# DE-020717_2.net
KiCad netlist of a schematic drawn in Altium Designer
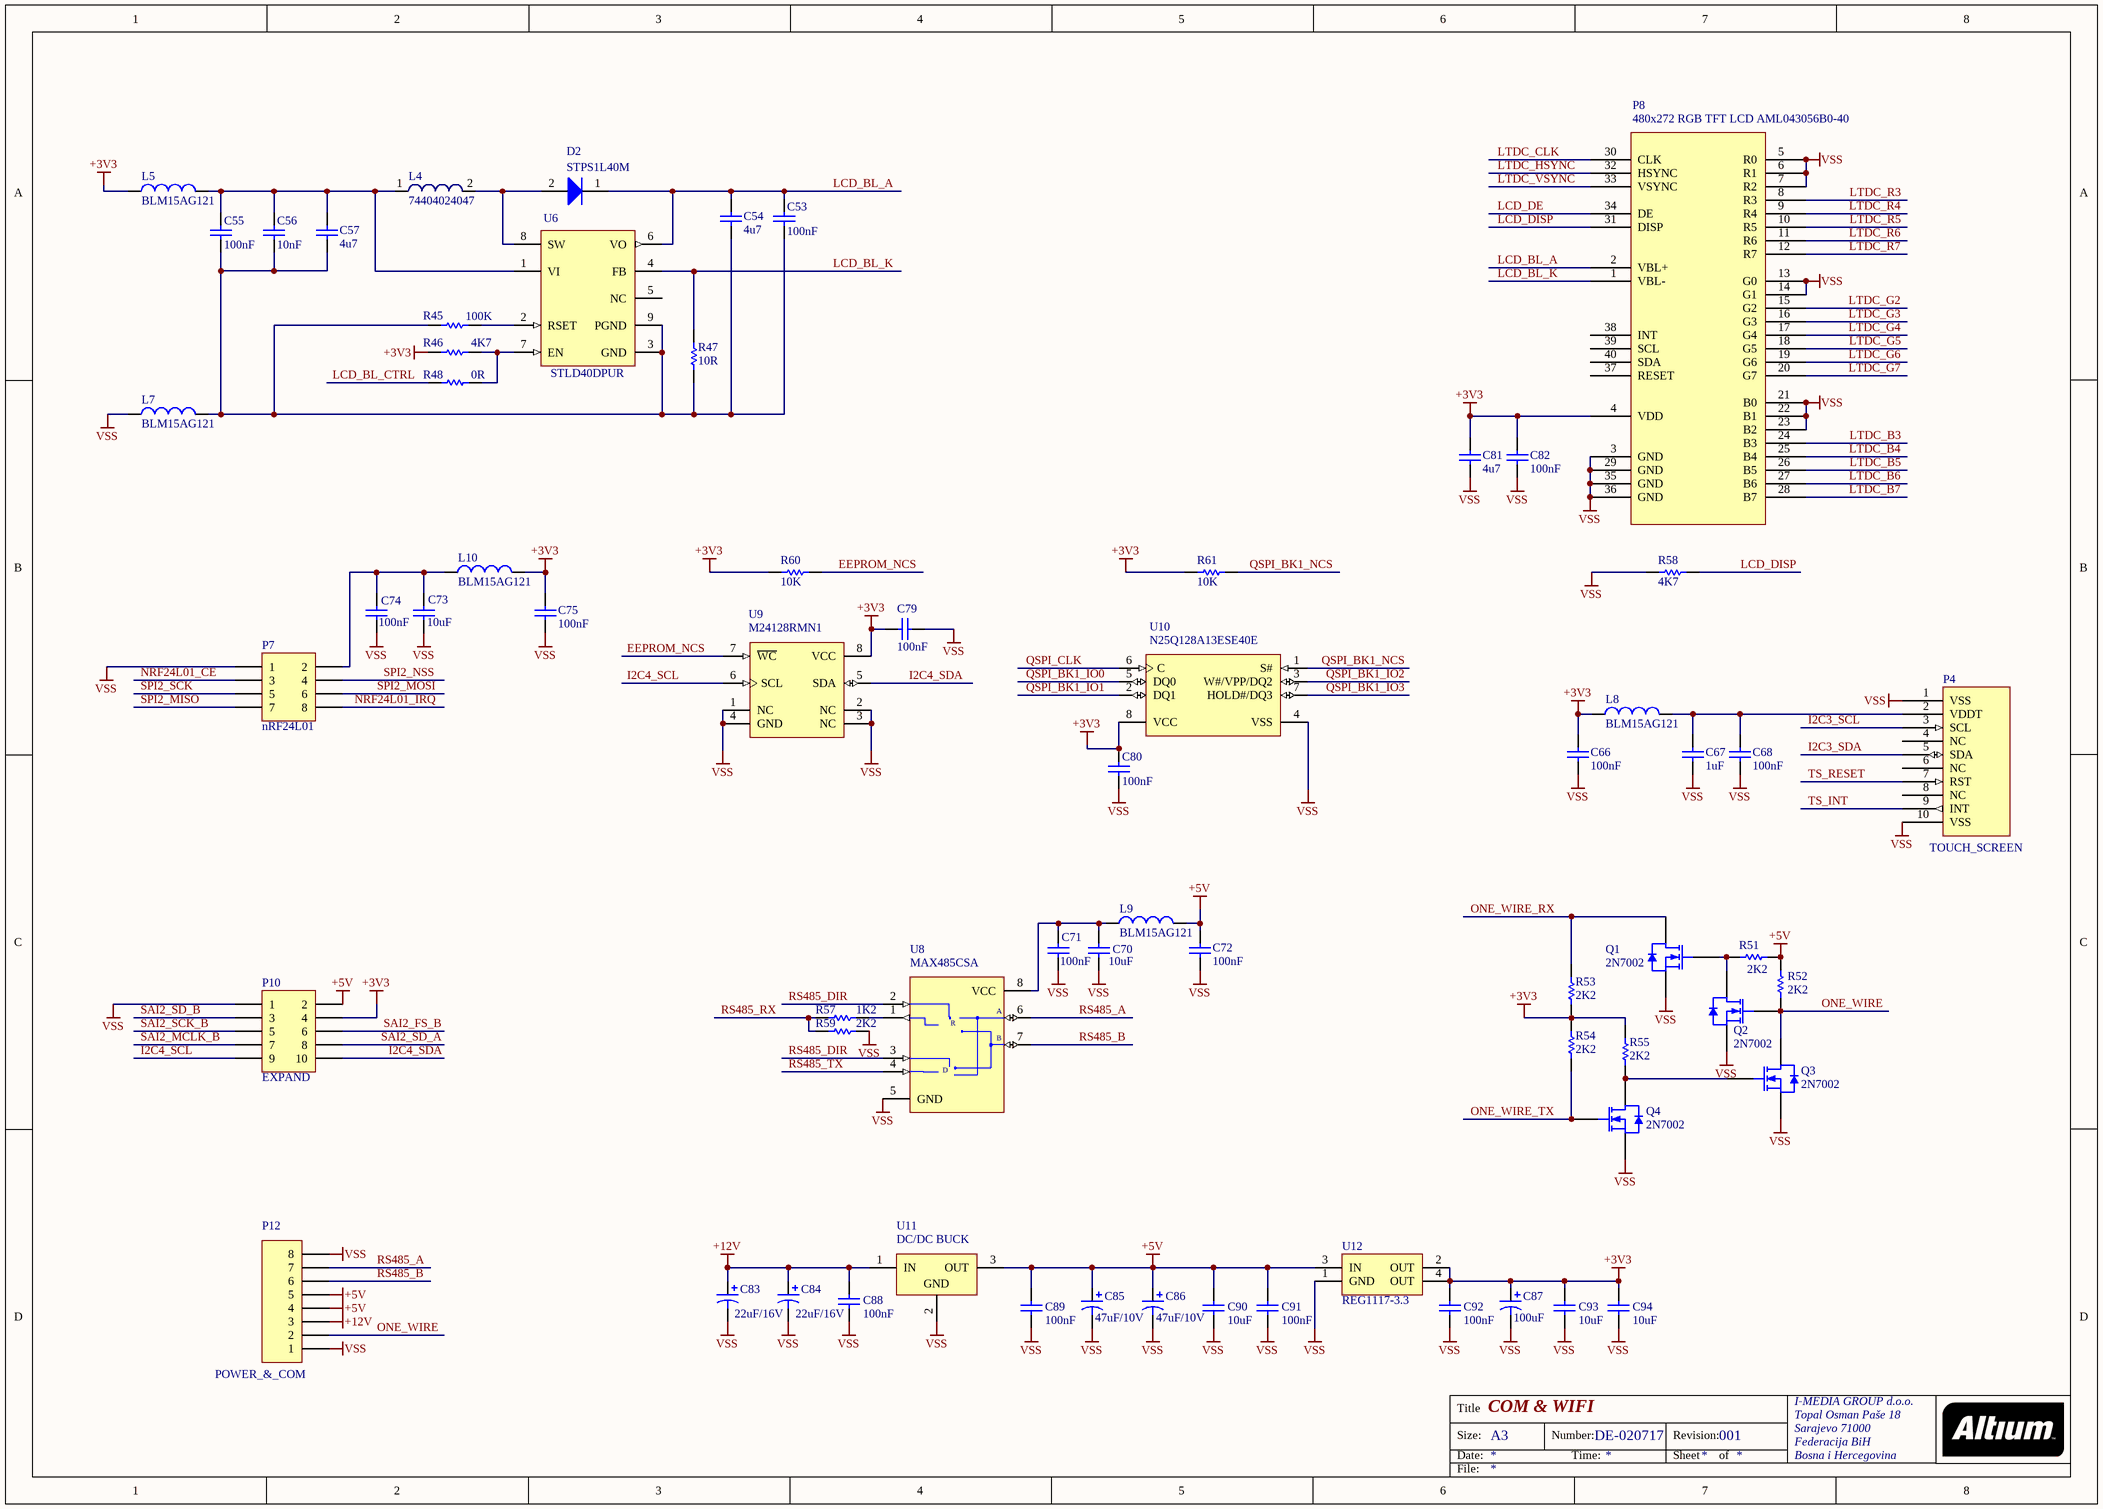
[diagram p0: DE-020717_2.SchDoc]

(export (version "E")
  (design (tool "Eeschema 10.0.6"))
  (components
    (comp (ref "C53")
      (value "100nF")
      (footprint "0603")
      (description "Ceramic Chip Capacitor - Standard")
      (fields (field (name "PUBLISHER") "Altium Limited"))
      (libsource (lib "KEMET Chip Capacitor") (part "C0603"))
    )
    (comp (ref "C54")
      (value "4u7")
      (footprint "0805")
      (description "Ceramic Chip Capacitor - Standard")
      (fields (field (name "PUBLISHER") "Altium Limited"))
      (libsource (lib "DE-020717") (part "C0805"))
    )
    (comp (ref "C55")
      (value "100nF")
      (footprint "0603")
      (description "Ceramic Chip Capacitor - Standard")
      (fields (field (name "PUBLISHER") "Altium Limited"))
      (libsource (lib "KEMET Chip Capacitor") (part "C0603"))
    )
    (comp (ref "C56")
      (value "10nF")
      (footprint "0603")
      (description "Ceramic Chip Capacitor - Standard")
      (fields (field (name "Comment") "100nF") (field (name "PUBLISHER") "Altium Limited"))
      (libsource (lib "KEMET Chip Capacitor") (part "C0603"))
    )
    (comp (ref "C57")
      (value "4u7")
      (footprint "0805")
      (description "Ceramic Chip Capacitor - Standard")
      (fields (field (name "PUBLISHER") "Altium Limited"))
      (libsource (lib "DE-020717") (part "C0805"))
    )
    (comp (ref "C66")
      (value "100nF")
      (footprint "0603")
      (description "Ceramic Chip Capacitor - Standard")
      (fields (field (name "PUBLISHER") "Altium Limited"))
      (libsource (lib "DE-020717") (part "C0603"))
    )
    (comp (ref "C67")
      (value "1uF")
      (footprint "0603")
      (description "Ceramic Chip Capacitor - Standard")
      (fields (field (name "PUBLISHER") "Altium Limited"))
      (libsource (lib "DE-020717") (part "C0603"))
    )
    (comp (ref "C68")
      (value "100nF")
      (footprint "0603")
      (description "Ceramic Chip Capacitor - Standard")
      (fields (field (name "PUBLISHER") "Altium Limited"))
      (libsource (lib "DE-020717") (part "C0603"))
    )
    (comp (ref "C70")
      (value "10uF")
      (footprint "0805")
      (description "Ceramic Chip Capacitor - Standard")
      (fields (field (name "Comment") "4u7") (field (name "PUBLISHER") "Altium Limited"))
      (libsource (lib "DE-020717") (part "C0805"))
    )
    (comp (ref "C71")
      (value "100nF")
      (footprint "0603")
      (description "Ceramic Chip Capacitor - Standard")
      (fields (field (name "PUBLISHER") "Altium Limited"))
      (libsource (lib "DE-020717") (part "C0603"))
    )
    (comp (ref "C72")
      (value "100nF")
      (footprint "0603")
      (description "Ceramic Chip Capacitor - Standard")
      (fields (field (name "PUBLISHER") "Altium Limited"))
      (libsource (lib "DE-020717") (part "C0603"))
    )
    (comp (ref "C73")
      (value "10uF")
      (footprint "0805")
      (description "Ceramic Chip Capacitor - Standard")
      (fields (field (name "Comment") "4u7") (field (name "PUBLISHER") "Altium Limited"))
      (libsource (lib "DE-020717") (part "C0805"))
    )
    (comp (ref "C74")
      (value "100nF")
      (footprint "0603")
      (description "Ceramic Chip Capacitor - Standard")
      (fields (field (name "PUBLISHER") "Altium Limited"))
      (libsource (lib "DE-020717") (part "C0603"))
    )
    (comp (ref "C75")
      (value "100nF")
      (footprint "0603")
      (description "Ceramic Chip Capacitor - Standard")
      (fields (field (name "PUBLISHER") "Altium Limited"))
      (libsource (lib "DE-020717") (part "C0603"))
    )
    (comp (ref "C79")
      (value "100nF")
      (footprint "0603")
      (description "Ceramic Chip Capacitor - Standard")
      (fields (field (name "PUBLISHER") "Altium Limited"))
      (libsource (lib "KEMET Chip Capacitor") (part "C0603"))
    )
    (comp (ref "C80")
      (value "100nF")
      (footprint "0603")
      (description "Ceramic Chip Capacitor - Standard")
      (fields (field (name "PUBLISHER") "Altium Limited"))
      (libsource (lib "KEMET Chip Capacitor") (part "C0603"))
    )
    (comp (ref "C81")
      (value "4u7")
      (footprint "0805")
      (description "Ceramic Chip Capacitor - Standard")
      (fields (field (name "PUBLISHER") "Altium Limited"))
      (libsource (lib "DE-020717") (part "C0805"))
    )
    (comp (ref "C82")
      (value "100nF")
      (footprint "0603")
      (description "Ceramic Chip Capacitor - Standard")
      (fields (field (name "PUBLISHER") "Altium Limited"))
      (libsource (lib "DE-020717") (part "C0603"))
    )
    (comp (ref "C83")
      (value "22uF/16V")
      (footprint "3528")
      (fields (field (name "PUBLISHER") "Altium Limited"))
      (libsource (lib "Vishay Sprague Tantalum Chip Capacitor") (part "293D156X0004B2"))
    )
    (comp (ref "C84")
      (value "22uF/16V")
      (footprint "3528")
      (fields (field (name "PUBLISHER") "Altium Limited"))
      (libsource (lib "Vishay Sprague Tantalum Chip Capacitor") (part "293D156X0004B2"))
    )
    (comp (ref "C85")
      (value "47uF/10V")
      (footprint "3528")
      (fields (field (name "PUBLISHER") "Altium Limited"))
      (libsource (lib "Vishay Sprague Tantalum Chip Capacitor") (part "293D156X0004B2"))
    )
    (comp (ref "C86")
      (value "47uF/10V")
      (footprint "3528")
      (fields (field (name "PUBLISHER") "Altium Limited"))
      (libsource (lib "Vishay Sprague Tantalum Chip Capacitor") (part "293D156X0004B2"))
    )
    (comp (ref "C87")
      (value "100uF")
      (footprint "3528")
      (fields (field (name "PUBLISHER") "Altium Limited"))
      (libsource (lib "Vishay Sprague Tantalum Chip Capacitor") (part "293D156X0004B2"))
    )
    (comp (ref "C88")
      (value "100nF")
      (footprint "0603")
      (description "Ceramic Chip Capacitor - Standard")
      (fields (field (name "PUBLISHER") "Altium Limited"))
      (libsource (lib "DE-251215") (part "C0603"))
    )
    (comp (ref "C89")
      (value "100nF")
      (footprint "0603")
      (description "Ceramic Chip Capacitor - Standard")
      (fields (field (name "PUBLISHER") "Altium Limited"))
      (libsource (lib "DE-251215") (part "C0603"))
    )
    (comp (ref "C90")
      (value "10uF")
      (footprint "0805")
      (description "Ceramic Chip Capacitor - Standard")
      (fields (field (name "PUBLISHER") "Altium Limited"))
      (libsource (lib "DE-251215") (part "C0805"))
    )
    (comp (ref "C91")
      (value "100nF")
      (footprint "0603")
      (description "Ceramic Chip Capacitor - Standard")
      (fields (field (name "PUBLISHER") "Altium Limited"))
      (libsource (lib "DE-251215") (part "C0603"))
    )
    (comp (ref "C92")
      (value "100nF")
      (footprint "0603")
      (description "Ceramic Chip Capacitor - Standard")
      (fields (field (name "PUBLISHER") "Altium Limited"))
      (libsource (lib "DE-251215") (part "C0603"))
    )
    (comp (ref "C93")
      (value "10uF")
      (footprint "0805")
      (description "Ceramic Chip Capacitor - Standard")
      (fields (field (name "PUBLISHER") "Altium Limited"))
      (libsource (lib "DE-251215") (part "C0805"))
    )
    (comp (ref "C94")
      (value "10uF")
      (footprint "0805")
      (description "Ceramic Chip Capacitor - Standard")
      (fields (field (name "PUBLISHER") "Altium Limited"))
      (libsource (lib "DE-251215") (part "C0805"))
    )
    (comp (ref "D2")
      (value "STPS1L40M")
      (footprint "ONSC-SOD-123-2-425-04_V")
      (description "Schottky Barrier Diode, 2-Pin SOD-123, Pb-Free, Tape and Reel")
      (fields (field (name "MANUFACTURER") "On Semiconductor") (field (name "PARTNUMBER") "SMMSD301T1G"))
      (libsource (lib "ON Semi Schottky Diodes & Schottky Rectifiers") (part "SMMSD301T1G"))
    )
    (comp (ref "L4")
      (value "74404024047")
      (footprint "WE-LQS 252012")
      (description "WE-LQS SMD Power Inductor, L=4.7 µH")
      (libsource (lib "WE-LQS SMD Power Inductor") (part "74404024047"))
    )
    (comp (ref "L5")
      (value "BLM15AG121")
      (footprint "0603")
      (description "Inductor")
      (fields (field (name "PUBLISHER") "Altium Limited"))
      (libsource (lib "DE-020717") (part "Inductor_SMD"))
    )
    (comp (ref "L7")
      (value "BLM15AG121")
      (footprint "0603")
      (description "Inductor")
      (fields (field (name "PUBLISHER") "Altium Limited"))
      (libsource (lib "DE-020717") (part "Inductor_SMD"))
    )
    (comp (ref "L8")
      (value "BLM15AG121")
      (footprint "0603")
      (description "Inductor")
      (fields (field (name "PUBLISHER") "Altium Limited"))
      (libsource (lib "DE-020717") (part "Inductor_SMD"))
    )
    (comp (ref "L9")
      (value "BLM15AG121")
      (footprint "0603")
      (description "Inductor")
      (fields (field (name "PUBLISHER") "Altium Limited"))
      (libsource (lib "DE-020717") (part "Inductor_SMD"))
    )
    (comp (ref "L10")
      (value "BLM15AG121")
      (footprint "0603")
      (description "Inductor")
      (fields (field (name "PUBLISHER") "Altium Limited"))
      (libsource (lib "DE-020717") (part "Inductor_SMD"))
    )
    (comp (ref "P4")
      (value "TOUCH_SCREEN")
      (footprint "10 pin PFC")
      (description "10 pin PFC connector bottom")
      (libsource (lib "DE-020717") (part "TS_Connector"))
    )
    (comp (ref "P7")
      (value "nRF24L01")
      (footprint "HDR2X4")
      (description "Header, 4-Pin, Dual row")
      (fields (field (name "PUBLISHER") "Altium Limited"))
      (libsource (lib "Miscellaneous Connectors") (part "Header 4X2"))
    )
    (comp (ref "P8")
      (value "480x272 RGB TFT LCD AML043056B0-40")
      (footprint "40 pin FPC")
      (description "40 pin pfc connector bottom")
      (libsource (lib "DE-020717") (part "TFT LCD Connector"))
    )
    (comp (ref "P10")
      (value "EXPAND")
      (footprint "HDR2X5")
      (description "Header, 5-Pin, Dual row")
      (fields (field (name "PUBLISHER") "Altium Limited"))
      (libsource (lib "Miscellaneous Connectors") (part "Header 5X2"))
    )
    (comp (ref "P12")
      (value "POWER_&_COM")
      (footprint "HDR1X8")
      (description "Header, 8-Pin")
      (fields (field (name "PUBLISHER") "Altium Limited"))
      (libsource (lib "Miscellaneous Connectors") (part "Header 8"))
    )
    (comp (ref "Q1")
      (value "2N7002")
      (footprint "SOT23_N")
      (description "N-channel Enhancement Mode Vertical D-MOSFET")
      (fields (field (name "PUBLISHER") "Altium Limited"))
      (libsource (lib "DE-290817") (part "BSS123"))
    )
    (comp (ref "Q2")
      (value "2N7002")
      (footprint "SOT23_N")
      (description "N-channel Enhancement Mode Vertical D-MOSFET")
      (fields (field (name "PUBLISHER") "Altium Limited"))
      (libsource (lib "DE-290817") (part "BSS123"))
    )
    (comp (ref "Q3")
      (value "2N7002")
      (footprint "SOT23_N")
      (description "N-channel Enhancement Mode Vertical D-MOSFET")
      (fields (field (name "PUBLISHER") "Altium Limited"))
      (libsource (lib "DE-290817") (part "BSS123"))
    )
    (comp (ref "Q4")
      (value "2N7002")
      (footprint "SOT23_N")
      (description "N-channel Enhancement Mode Vertical D-MOSFET")
      (fields (field (name "PUBLISHER") "Altium Limited"))
      (libsource (lib "DE-290817") (part "BSS123"))
    )
    (comp (ref "R45")
      (value "100K")
      (footprint "ERA-0603")
      (fields (field (name "PUBLISHER") "Altium Limited"))
      (libsource (lib "DE-020717") (part "ERAV"))
    )
    (comp (ref "R46")
      (value "4K7")
      (footprint "ERA-0603")
      (fields (field (name "PUBLISHER") "Altium Limited"))
      (libsource (lib "DE-020717") (part "ERAV"))
    )
    (comp (ref "R47")
      (value "10R")
      (footprint "ERA-0805")
      (fields (field (name "PUBLISHER") "Altium Limited"))
      (libsource (lib "Panasonic Resistor") (part "ERAS"))
    )
    (comp (ref "R48")
      (value "0R")
      (footprint "ERA-0603")
      (fields (field (name "PUBLISHER") "Altium Limited"))
      (libsource (lib "DE-020717") (part "ERAV"))
    )
    (comp (ref "R51")
      (value "2K2")
      (footprint "ERA-0603")
      (fields (field (name "PUBLISHER") "Altium Limited"))
      (libsource (lib "DE-200216_03") (part "ERAV"))
    )
    (comp (ref "R52")
      (value "2K2")
      (footprint "ERA-0603")
      (fields (field (name "PUBLISHER") "Altium Limited"))
      (libsource (lib "DE-200216_03") (part "ERAV"))
    )
    (comp (ref "R53")
      (value "2K2")
      (footprint "ERA-0603")
      (fields (field (name "PUBLISHER") "Altium Limited"))
      (libsource (lib "DE-290817") (part "ERAV"))
    )
    (comp (ref "R54")
      (value "2K2")
      (footprint "ERA-0603")
      (fields (field (name "PUBLISHER") "Altium Limited"))
      (libsource (lib "DE-200216_03") (part "ERAV"))
    )
    (comp (ref "R55")
      (value "2K2")
      (footprint "ERA-0603")
      (fields (field (name "PUBLISHER") "Altium Limited"))
      (libsource (lib "DE-200216_03") (part "ERAV"))
    )
    (comp (ref "R57")
      (value "1K2")
      (footprint "ERA-0603")
      (fields (field (name "PUBLISHER") "Altium Limited"))
      (libsource (lib "Panasonic Resistor") (part "ERA3Y"))
    )
    (comp (ref "R58")
      (value "4K7")
      (footprint "ERA-0603")
      (fields (field (name "PUBLISHER") "Altium Limited"))
      (libsource (lib "Panasonic Resistor") (part "ERA3Y"))
    )
    (comp (ref "R59")
      (value "2K2")
      (footprint "ERA-0603")
      (fields (field (name "PUBLISHER") "Altium Limited"))
      (libsource (lib "Panasonic Resistor") (part "ERA3Y"))
    )
    (comp (ref "R60")
      (value "10K")
      (footprint "ERA-0603")
      (fields (field (name "PUBLISHER") "Altium Limited"))
      (libsource (lib "Panasonic Resistor") (part "ERA3Y"))
    )
    (comp (ref "R61")
      (value "10K")
      (footprint "ERA-0603")
      (fields (field (name "PUBLISHER") "Altium Limited"))
      (libsource (lib "Panasonic Resistor") (part "ERA3Y"))
    )
    (comp (ref "U6")
      (value "STLD40DPUR")
      (footprint "QFN8_V")
      (description "White Led Power Supply For Large Display Backlight, 8-Pin VFDFPN, Tape and Reel")
      (libsource (lib "STMicroelectronics Power Management Switching Regulator") (part "STLD40DPUR"))
    )
    (comp (ref "U8")
      (value "MAX485CSA")
      (footprint "NSO8_N")
      (description "Low-Power, Slew-Rate-Limited RS-485/RS-422 Transceiver")
      (fields (field (name "PUBLISHER") "Altium Limited"))
      (libsource (lib "Maxim Communication Transceiver") (part "MAX485CSA"))
    )
    (comp (ref "U9")
      (value "M24128RMN1")
      (footprint "SOP8_N")
      (description "128 K Serial I˛C Bus EEPROM")
      (fields (field (name "PUBLISHER") "Altium Limited"))
      (libsource (lib "ST Memory EEPROM Serial") (part "M24128RMN1"))
    )
    (comp (ref "U10")
      (value "N25Q128A13ESE40E")
      (footprint "MICT-SE-8_N")
      (fields (field (name "VOLTAGE") "2.7V-3.6V ") (field (name "MANUFACTURER") "Micron"))
      (libsource (lib "Micron Memory Serial NOR Flash") (part "N25Q128A13ESE40E"))
    )
    (comp (ref "U11")
      (value "DC/DC BUCK")
      (footprint "TO220")
      (description "Positive Voltage Regulator, 5V, 3-Pin TO-220")
      (fields (field (name "PARTNUMBER") "L7805CV"))
      (libsource (lib "DE-020717") (part "L7805CV"))
    )
    (comp (ref "U12")
      (value "REG1117-3.3")
      (footprint "ZZ311")
      (description "800mA and 1A Low Dropout Positive Regulator 2.85V, 3.3V, 5V, and Adjustable")
      (fields (field (name "PUBLISHER") "Altium Limited"))
      (libsource (lib "DE-251215") (part "REG1117-3.3"))
    )
  )
  (nets
    (net (code "1") (name "+3V3") (class "Default")
      (node (ref "C66") (pin "2") (pinfunction "2_2") (pintype "passive"))
      (node (ref "C75") (pin "2") (pinfunction "2_2") (pintype "passive"))
      (node (ref "C79") (pin "2") (pinfunction "2_2") (pintype "passive"))
      (node (ref "C80") (pin "1") (pinfunction "1_1") (pintype "passive"))
      (node (ref "C81") (pin "2") (pinfunction "2_2") (pintype "passive"))
      (node (ref "C82") (pin "2") (pinfunction "2_2") (pintype "passive"))
      (node (ref "C87") (pin "1") (pinfunction "1_1") (pintype "passive"))
      (node (ref "C92") (pin "2") (pinfunction "2_2") (pintype "passive"))
      (node (ref "C93") (pin "2") (pinfunction "2_2") (pintype "passive"))
      (node (ref "C94") (pin "2") (pinfunction "2_2") (pintype "passive"))
      (node (ref "L10") (pin "2") (pinfunction "2_2") (pintype "passive"))
      (node (ref "L5") (pin "1") (pinfunction "1_1") (pintype "passive"))
      (node (ref "L8") (pin "1") (pinfunction "1_1") (pintype "passive"))
      (node (ref "P10") (pin "4") (pinfunction "4_4") (pintype "passive"))
      (node (ref "P8") (pin "4") (pinfunction "VDD_4") (pintype "passive"))
      (node (ref "R46") (pin "2") (pinfunction "2_2") (pintype "passive"))
      (node (ref "R53") (pin "1") (pinfunction "1_1") (pintype "passive"))
      (node (ref "R54") (pin "2") (pinfunction "2_2") (pintype "passive"))
      (node (ref "R55") (pin "2") (pinfunction "2_2") (pintype "passive"))
      (node (ref "R60") (pin "1") (pinfunction "1_1") (pintype "passive"))
      (node (ref "R61") (pin "1") (pinfunction "1_1") (pintype "passive"))
      (node (ref "U10") (pin "8") (pinfunction "VCC_8") (pintype "power_in"))
      (node (ref "U12") (pin "2") (pinfunction "OUT_2") (pintype "power_in"))
      (node (ref "U12") (pin "4") (pinfunction "OUT_4") (pintype "power_in"))
      (node (ref "U9") (pin "8") (pinfunction "VCC_8") (pintype "power_in"))
    )
    (net (code "2") (name "+5V") (class "Default")
      (node (ref "C72") (pin "2") (pinfunction "2_2") (pintype "passive"))
      (node (ref "C85") (pin "1") (pinfunction "1_1") (pintype "passive"))
      (node (ref "C86") (pin "1") (pinfunction "1_1") (pintype "passive"))
      (node (ref "C89") (pin "2") (pinfunction "2_2") (pintype "passive"))
      (node (ref "C90") (pin "2") (pinfunction "2_2") (pintype "passive"))
      (node (ref "C91") (pin "2") (pinfunction "2_2") (pintype "passive"))
      (node (ref "L9") (pin "2") (pinfunction "2_2") (pintype "passive"))
      (node (ref "P10") (pin "2") (pinfunction "2_2") (pintype "passive"))
      (node (ref "P12") (pin "4") (pinfunction "4_4") (pintype "passive"))
      (node (ref "P12") (pin "5") (pinfunction "5_5") (pintype "passive"))
      (node (ref "R51") (pin "1") (pinfunction "1_1") (pintype "passive"))
      (node (ref "R52") (pin "2") (pinfunction "2_2") (pintype "passive"))
      (node (ref "U11") (pin "3") (pinfunction "OUT_3") (pintype "power_in"))
      (node (ref "U12") (pin "3") (pinfunction "IN_3") (pintype "power_in"))
    )
    (net (code "3") (name "+12V") (class "Default")
      (node (ref "C83") (pin "1") (pinfunction "1_1") (pintype "passive"))
      (node (ref "C84") (pin "1") (pinfunction "1_1") (pintype "passive"))
      (node (ref "C88") (pin "2") (pinfunction "2_2") (pintype "passive"))
      (node (ref "P12") (pin "3") (pinfunction "3_3") (pintype "passive"))
      (node (ref "U11") (pin "1") (pinfunction "IN_1") (pintype "power_in"))
    )
    (net (code "4") (name "/EEPROM_NCS") (class "Default")
      (node (ref "R60") (pin "2") (pinfunction "2_2") (pintype "passive"))
      (node (ref "U9") (pin "7") (pinfunction "~{WC}_7") (pintype "input"))
    )
    (net (code "5") (name "/I2C3_SCL") (class "Default")
      (node (ref "P4") (pin "3") (pinfunction "SCL_3") (pintype "input"))
    )
    (net (code "6") (name "/I2C3_SDA") (class "Default")
      (node (ref "P4") (pin "5") (pinfunction "SDA_5") (pintype "bidirectional"))
    )
    (net (code "7") (name "/I2C4_SCL") (class "Default")
      (node (ref "P10") (pin "9") (pinfunction "9_9") (pintype "passive"))
      (node (ref "U9") (pin "6") (pinfunction "SCL_6") (pintype "input"))
    )
    (net (code "8") (name "/I2C4_SDA") (class "Default")
      (node (ref "P10") (pin "10") (pinfunction "10_10") (pintype "passive"))
      (node (ref "U9") (pin "5") (pinfunction "SDA_5") (pintype "bidirectional"))
    )
    (net (code "9") (name "/LCD_BL_A") (class "Default")
      (node (ref "C53") (pin "1") (pinfunction "1_1") (pintype "passive"))
      (node (ref "C54") (pin "2") (pinfunction "2_2") (pintype "passive"))
      (node (ref "D2") (pin "1") (pinfunction "K_1") (pintype "passive"))
      (node (ref "P8") (pin "2") (pinfunction "VBL+_2") (pintype "passive"))
      (node (ref "U6") (pin "6") (pinfunction "VO_6") (pintype "output"))
    )
    (net (code "10") (name "/LCD_BL_CTRL") (class "Default")
      (node (ref "R48") (pin "2") (pinfunction "2_2") (pintype "passive"))
    )
    (net (code "11") (name "/LCD_BL_K") (class "Default")
      (node (ref "P8") (pin "1") (pinfunction "VBL-_1") (pintype "passive"))
      (node (ref "R47") (pin "2") (pinfunction "2_2") (pintype "passive"))
      (node (ref "U6") (pin "4") (pinfunction "FB_4") (pintype "passive"))
    )
    (net (code "12") (name "/LCD_DE") (class "Default")
      (node (ref "P8") (pin "34") (pinfunction "DE_34") (pintype "passive"))
    )
    (net (code "13") (name "/LCD_DISP") (class "Default")
      (node (ref "P8") (pin "31") (pinfunction "DISP_31") (pintype "passive"))
      (node (ref "R58") (pin "2") (pinfunction "2_2") (pintype "passive"))
    )
    (net (code "14") (name "/LTDC_B3") (class "Default")
      (node (ref "P8") (pin "24") (pinfunction "B3_24") (pintype "passive"))
    )
    (net (code "15") (name "/LTDC_B4") (class "Default")
      (node (ref "P8") (pin "25") (pinfunction "B4_25") (pintype "passive"))
    )
    (net (code "16") (name "/LTDC_B5") (class "Default")
      (node (ref "P8") (pin "26") (pinfunction "B5_26") (pintype "passive"))
    )
    (net (code "17") (name "/LTDC_B6") (class "Default")
      (node (ref "P8") (pin "27") (pinfunction "B6_27") (pintype "passive"))
    )
    (net (code "18") (name "/LTDC_B7") (class "Default")
      (node (ref "P8") (pin "28") (pinfunction "B7_28") (pintype "passive"))
    )
    (net (code "19") (name "/LTDC_CLK") (class "Default")
      (node (ref "P8") (pin "30") (pinfunction "CLK_30") (pintype "passive"))
    )
    (net (code "20") (name "/LTDC_G2") (class "Default")
      (node (ref "P8") (pin "15") (pinfunction "G2_15") (pintype "passive"))
    )
    (net (code "21") (name "/LTDC_G3") (class "Default")
      (node (ref "P8") (pin "16") (pinfunction "G3_16") (pintype "passive"))
    )
    (net (code "22") (name "/LTDC_G4") (class "Default")
      (node (ref "P8") (pin "17") (pinfunction "G4_17") (pintype "passive"))
    )
    (net (code "23") (name "/LTDC_G5") (class "Default")
      (node (ref "P8") (pin "18") (pinfunction "G5_18") (pintype "passive"))
    )
    (net (code "24") (name "/LTDC_G6") (class "Default")
      (node (ref "P8") (pin "19") (pinfunction "G6_19") (pintype "passive"))
    )
    (net (code "25") (name "/LTDC_G7") (class "Default")
      (node (ref "P8") (pin "20") (pinfunction "G7_20") (pintype "passive"))
    )
    (net (code "26") (name "/LTDC_HSYNC") (class "Default")
      (node (ref "P8") (pin "32") (pinfunction "HSYNC_32") (pintype "passive"))
    )
    (net (code "27") (name "/LTDC_R3") (class "Default")
      (node (ref "P8") (pin "8") (pinfunction "R3_8") (pintype "passive"))
    )
    (net (code "28") (name "/LTDC_R4") (class "Default")
      (node (ref "P8") (pin "9") (pinfunction "R4_9") (pintype "passive"))
    )
    (net (code "29") (name "/LTDC_R5") (class "Default")
      (node (ref "P8") (pin "10") (pinfunction "R5_10") (pintype "passive"))
    )
    (net (code "30") (name "/LTDC_R6") (class "Default")
      (node (ref "P8") (pin "11") (pinfunction "R6_11") (pintype "passive"))
    )
    (net (code "31") (name "/LTDC_R7") (class "Default")
      (node (ref "P8") (pin "12") (pinfunction "R7_12") (pintype "passive"))
    )
    (net (code "32") (name "/LTDC_VSYNC") (class "Default")
      (node (ref "P8") (pin "33") (pinfunction "VSYNC_33") (pintype "passive"))
    )
    (net (code "33") (name "/NRF24L01_CE") (class "Default")
      (node (ref "P7") (pin "3") (pinfunction "3_3") (pintype "passive"))
    )
    (net (code "34") (name "/NRF24L01_IRQ") (class "Default")
      (node (ref "P7") (pin "8") (pinfunction "8_8") (pintype "passive"))
    )
    (net (code "35") (name "/ONE_WIRE") (class "Default")
      (node (ref "P12") (pin "2") (pinfunction "2_2") (pintype "passive"))
      (node (ref "Q2") (pin "1") (pinfunction "G_1") (pintype "passive"))
      (node (ref "Q3") (pin "3") (pinfunction "D_3") (pintype "passive"))
      (node (ref "R52") (pin "1") (pinfunction "1_1") (pintype "passive"))
    )
    (net (code "36") (name "/ONE_WIRE_RX") (class "Default")
      (node (ref "Q1") (pin "3") (pinfunction "D_3") (pintype "passive"))
      (node (ref "R53") (pin "2") (pinfunction "2_2") (pintype "passive"))
    )
    (net (code "37") (name "/ONE_WIRE_TX") (class "Default")
      (node (ref "Q4") (pin "1") (pinfunction "G_1") (pintype "passive"))
      (node (ref "R54") (pin "1") (pinfunction "1_1") (pintype "passive"))
    )
    (net (code "38") (name "/QSPI_BK1_IO0") (class "Default")
      (node (ref "U10") (pin "5") (pinfunction "DQ0_5") (pintype "bidirectional"))
    )
    (net (code "39") (name "/QSPI_BK1_IO1") (class "Default")
      (node (ref "U10") (pin "2") (pinfunction "DQ1_2") (pintype "bidirectional"))
    )
    (net (code "40") (name "/QSPI_BK1_IO2") (class "Default")
      (node (ref "U10") (pin "3") (pinfunction "W#/VPP/DQ2_3") (pintype "bidirectional"))
    )
    (net (code "41") (name "/QSPI_BK1_IO3") (class "Default")
      (node (ref "U10") (pin "7") (pinfunction "HOLD#/DQ3_7") (pintype "bidirectional"))
    )
    (net (code "42") (name "/QSPI_BK1_NCS") (class "Default")
      (node (ref "R61") (pin "2") (pinfunction "2_2") (pintype "passive"))
      (node (ref "U10") (pin "1") (pinfunction "S#_1") (pintype "input"))
    )
    (net (code "43") (name "/QSPI_CLK") (class "Default")
      (node (ref "U10") (pin "6") (pinfunction "C_6") (pintype "input"))
    )
    (net (code "44") (name "/RS485_A") (class "Default")
      (node (ref "P12") (pin "7") (pinfunction "7_7") (pintype "passive"))
      (node (ref "U8") (pin "6") (pinfunction "A_6") (pintype "bidirectional"))
    )
    (net (code "45") (name "/RS485_B") (class "Default")
      (node (ref "P12") (pin "6") (pinfunction "6_6") (pintype "passive"))
      (node (ref "U8") (pin "7") (pinfunction "B_7") (pintype "bidirectional"))
    )
    (net (code "46") (name "/RS485_DIR") (class "Default")
      (node (ref "U8") (pin "2") (pinfunction "~{RE}_2") (pintype "input"))
      (node (ref "U8") (pin "3") (pinfunction "DE_3") (pintype "input"))
    )
    (net (code "47") (name "/RS485_RX") (class "Default")
      (node (ref "R57") (pin "1") (pinfunction "1_1") (pintype "passive"))
      (node (ref "R59") (pin "1") (pinfunction "1_1") (pintype "passive"))
    )
    (net (code "48") (name "/RS485_TX") (class "Default")
      (node (ref "U8") (pin "4") (pinfunction "DI_4") (pintype "input"))
    )
    (net (code "49") (name "/SAI2_FS_B") (class "Default")
      (node (ref "P10") (pin "6") (pinfunction "6_6") (pintype "passive"))
    )
    (net (code "50") (name "/SAI2_MCLK_B") (class "Default")
      (node (ref "P10") (pin "7") (pinfunction "7_7") (pintype "passive"))
    )
    (net (code "51") (name "/SAI2_SCK_B") (class "Default")
      (node (ref "P10") (pin "5") (pinfunction "5_5") (pintype "passive"))
    )
    (net (code "52") (name "/SAI2_SD_A") (class "Default")
      (node (ref "P10") (pin "8") (pinfunction "8_8") (pintype "passive"))
    )
    (net (code "53") (name "/SAI2_SD_B") (class "Default")
      (node (ref "P10") (pin "3") (pinfunction "3_3") (pintype "passive"))
    )
    (net (code "54") (name "/SPI2_MISO") (class "Default")
      (node (ref "P7") (pin "7") (pinfunction "7_7") (pintype "passive"))
    )
    (net (code "55") (name "/SPI2_MOSI") (class "Default")
      (node (ref "P7") (pin "6") (pinfunction "6_6") (pintype "passive"))
    )
    (net (code "56") (name "/SPI2_NSS") (class "Default")
      (node (ref "P7") (pin "4") (pinfunction "4_4") (pintype "passive"))
    )
    (net (code "57") (name "/SPI2_SCK") (class "Default")
      (node (ref "P7") (pin "5") (pinfunction "5_5") (pintype "passive"))
    )
    (net (code "58") (name "/TS_INT") (class "Default")
      (node (ref "P4") (pin "9") (pinfunction "INT_9") (pintype "output"))
    )
    (net (code "59") (name "/TS_RESET") (class "Default")
      (node (ref "P4") (pin "7") (pinfunction "RST_7") (pintype "input"))
    )
    (net (code "60") (name "Net-(C73-Pad2)") (class "Default")
      (node (ref "C73") (pin "2") (pinfunction "2_2") (pintype "passive"))
      (node (ref "C74") (pin "2") (pinfunction "2_2") (pintype "passive"))
      (node (ref "L10") (pin "1") (pinfunction "1_1") (pintype "passive"))
      (node (ref "P7") (pin "2") (pinfunction "2_2") (pintype "passive"))
    )
    (net (code "61") (name "Net-(D2-A)") (class "Default")
      (node (ref "D2") (pin "2") (pinfunction "A_2") (pintype "passive"))
      (node (ref "L4") (pin "2") (pinfunction "2_2") (pintype "passive"))
      (node (ref "U6") (pin "8") (pinfunction "SW_8") (pintype "open_collector"))
    )
    (net (code "62") (name "Net-(P4-VDDT)") (class "Default")
      (node (ref "C67") (pin "2") (pinfunction "2_2") (pintype "passive"))
      (node (ref "C68") (pin "2") (pinfunction "2_2") (pintype "passive"))
      (node (ref "L8") (pin "2") (pinfunction "2_2") (pintype "passive"))
      (node (ref "P4") (pin "2") (pinfunction "VDDT_2") (pintype "power_in"))
    )
    (net (code "63") (name "Net-(Q1-G)") (class "Default")
      (node (ref "Q1") (pin "1") (pinfunction "G_1") (pintype "passive"))
      (node (ref "Q2") (pin "3") (pinfunction "D_3") (pintype "passive"))
      (node (ref "R51") (pin "2") (pinfunction "2_2") (pintype "passive"))
    )
    (net (code "64") (name "Net-(Q3-G)") (class "Default")
      (node (ref "Q3") (pin "1") (pinfunction "G_1") (pintype "passive"))
      (node (ref "Q4") (pin "3") (pinfunction "D_3") (pintype "passive"))
      (node (ref "R55") (pin "1") (pinfunction "1_1") (pintype "passive"))
    )
    (net (code "65") (name "Net-(U6-EN)") (class "Default")
      (node (ref "R46") (pin "1") (pinfunction "1_1") (pintype "passive"))
      (node (ref "R48") (pin "1") (pinfunction "1_1") (pintype "passive"))
      (node (ref "U6") (pin "7") (pinfunction "EN_7") (pintype "input"))
    )
    (net (code "66") (name "Net-(U6-GND)") (class "Default")
      (node (ref "C53") (pin "2") (pinfunction "2_2") (pintype "passive"))
      (node (ref "C54") (pin "1") (pinfunction "1_1") (pintype "passive"))
      (node (ref "C55") (pin "2") (pinfunction "2_2") (pintype "passive"))
      (node (ref "C56") (pin "2") (pinfunction "2_2") (pintype "passive"))
      (node (ref "C57") (pin "2") (pinfunction "2_2") (pintype "passive"))
      (node (ref "L7") (pin "2") (pinfunction "2_2") (pintype "passive"))
      (node (ref "R45") (pin "2") (pinfunction "2_2") (pintype "passive"))
      (node (ref "R47") (pin "1") (pinfunction "1_1") (pintype "passive"))
      (node (ref "U6") (pin "3") (pinfunction "GND_3") (pintype "power_in"))
      (node (ref "U6") (pin "9") (pinfunction "PGND_9") (pintype "power_in"))
    )
    (net (code "67") (name "Net-(U6-RSET)") (class "Default")
      (node (ref "R45") (pin "1") (pinfunction "1_1") (pintype "passive"))
      (node (ref "U6") (pin "2") (pinfunction "RSET_2") (pintype "input"))
    )
    (net (code "68") (name "Net-(U6-VI)") (class "Default")
      (node (ref "C55") (pin "1") (pinfunction "1_1") (pintype "passive"))
      (node (ref "C56") (pin "1") (pinfunction "1_1") (pintype "passive"))
      (node (ref "C57") (pin "1") (pinfunction "1_1") (pintype "passive"))
      (node (ref "L4") (pin "1") (pinfunction "1_1") (pintype "passive"))
      (node (ref "L5") (pin "2") (pinfunction "2_2") (pintype "passive"))
      (node (ref "U6") (pin "1") (pinfunction "VI_1") (pintype "power_in"))
    )
    (net (code "69") (name "Net-(U8-RO)") (class "Default")
      (node (ref "R57") (pin "2") (pinfunction "2_2") (pintype "passive"))
      (node (ref "U8") (pin "1") (pinfunction "RO_1") (pintype "output"))
    )
    (net (code "70") (name "Net-(U8-VCC)") (class "Default")
      (node (ref "C70") (pin "2") (pinfunction "2_2") (pintype "passive"))
      (node (ref "C71") (pin "2") (pinfunction "2_2") (pintype "passive"))
      (node (ref "L9") (pin "1") (pinfunction "1_1") (pintype "passive"))
      (node (ref "U8") (pin "8") (pinfunction "VCC_8") (pintype "power_in"))
    )
    (net (code "71") (name "VSS") (class "Default")
      (node (ref "C66") (pin "1") (pinfunction "1_1") (pintype "passive"))
      (node (ref "C67") (pin "1") (pinfunction "1_1") (pintype "passive"))
      (node (ref "C68") (pin "1") (pinfunction "1_1") (pintype "passive"))
      (node (ref "C70") (pin "1") (pinfunction "1_1") (pintype "passive"))
      (node (ref "C71") (pin "1") (pinfunction "1_1") (pintype "passive"))
      (node (ref "C72") (pin "1") (pinfunction "1_1") (pintype "passive"))
      (node (ref "C73") (pin "1") (pinfunction "1_1") (pintype "passive"))
      (node (ref "C74") (pin "1") (pinfunction "1_1") (pintype "passive"))
      (node (ref "C75") (pin "1") (pinfunction "1_1") (pintype "passive"))
      (node (ref "C79") (pin "1") (pinfunction "1_1") (pintype "passive"))
      (node (ref "C80") (pin "2") (pinfunction "2_2") (pintype "passive"))
      (node (ref "C81") (pin "1") (pinfunction "1_1") (pintype "passive"))
      (node (ref "C82") (pin "1") (pinfunction "1_1") (pintype "passive"))
      (node (ref "C83") (pin "2") (pinfunction "2_2") (pintype "passive"))
      (node (ref "C84") (pin "2") (pinfunction "2_2") (pintype "passive"))
      (node (ref "C85") (pin "2") (pinfunction "2_2") (pintype "passive"))
      (node (ref "C86") (pin "2") (pinfunction "2_2") (pintype "passive"))
      (node (ref "C87") (pin "2") (pinfunction "2_2") (pintype "passive"))
      (node (ref "C88") (pin "1") (pinfunction "1_1") (pintype "passive"))
      (node (ref "C89") (pin "1") (pinfunction "1_1") (pintype "passive"))
      (node (ref "C90") (pin "1") (pinfunction "1_1") (pintype "passive"))
      (node (ref "C91") (pin "1") (pinfunction "1_1") (pintype "passive"))
      (node (ref "C92") (pin "1") (pinfunction "1_1") (pintype "passive"))
      (node (ref "C93") (pin "1") (pinfunction "1_1") (pintype "passive"))
      (node (ref "C94") (pin "1") (pinfunction "1_1") (pintype "passive"))
      (node (ref "L7") (pin "1") (pinfunction "1_1") (pintype "passive"))
      (node (ref "P10") (pin "1") (pinfunction "1_1") (pintype "passive"))
      (node (ref "P12") (pin "1") (pinfunction "1_1") (pintype "passive"))
      (node (ref "P12") (pin "8") (pinfunction "8_8") (pintype "passive"))
      (node (ref "P4") (pin "1") (pinfunction "VSS_1") (pintype "power_in"))
      (node (ref "P4") (pin "10") (pinfunction "VSS_10") (pintype "power_in"))
      (node (ref "P7") (pin "1") (pinfunction "1_1") (pintype "passive"))
      (node (ref "P8") (pin "13") (pinfunction "G0_13") (pintype "passive"))
      (node (ref "P8") (pin "14") (pinfunction "G1_14") (pintype "passive"))
      (node (ref "P8") (pin "21") (pinfunction "B0_21") (pintype "passive"))
      (node (ref "P8") (pin "22") (pinfunction "B1_22") (pintype "passive"))
      (node (ref "P8") (pin "23") (pinfunction "B2_23") (pintype "passive"))
      (node (ref "P8") (pin "29") (pinfunction "GND_29") (pintype "passive"))
      (node (ref "P8") (pin "3") (pinfunction "GND_3") (pintype "passive"))
      (node (ref "P8") (pin "35") (pinfunction "GND_35") (pintype "passive"))
      (node (ref "P8") (pin "36") (pinfunction "GND_36") (pintype "passive"))
      (node (ref "P8") (pin "5") (pinfunction "R0_5") (pintype "passive"))
      (node (ref "P8") (pin "6") (pinfunction "R1_6") (pintype "passive"))
      (node (ref "P8") (pin "7") (pinfunction "R2_7") (pintype "passive"))
      (node (ref "Q1") (pin "2") (pinfunction "S_2") (pintype "passive"))
      (node (ref "Q2") (pin "2") (pinfunction "S_2") (pintype "passive"))
      (node (ref "Q3") (pin "2") (pinfunction "S_2") (pintype "passive"))
      (node (ref "Q4") (pin "2") (pinfunction "S_2") (pintype "passive"))
      (node (ref "R58") (pin "1") (pinfunction "1_1") (pintype "passive"))
      (node (ref "R59") (pin "2") (pinfunction "2_2") (pintype "passive"))
      (node (ref "U10") (pin "4") (pinfunction "VSS_4") (pintype "power_in"))
      (node (ref "U11") (pin "2") (pinfunction "GND_2") (pintype "power_in"))
      (node (ref "U12") (pin "1") (pinfunction "GND_1") (pintype "power_in"))
      (node (ref "U8") (pin "5") (pinfunction "GND_5") (pintype "power_in"))
      (node (ref "U9") (pin "1") (pinfunction "NC_1") (pintype "passive"))
      (node (ref "U9") (pin "2") (pinfunction "NC_2") (pintype "passive"))
      (node (ref "U9") (pin "3") (pinfunction "NC_3") (pintype "passive"))
      (node (ref "U9") (pin "4") (pinfunction "GND_4") (pintype "power_in"))
    )
    (net (code "72") (name "unconnected-(P4-NC-Pad4)") (class "Default")
      (node (ref "P4") (pin "4") (pinfunction "NC_4") (pintype "passive"))
    )
    (net (code "73") (name "unconnected-(P4-NC-Pad6)") (class "Default")
      (node (ref "P4") (pin "6") (pinfunction "NC_6") (pintype "passive"))
    )
    (net (code "74") (name "unconnected-(P4-NC-Pad8)") (class "Default")
      (node (ref "P4") (pin "8") (pinfunction "NC_8") (pintype "passive"))
    )
    (net (code "75") (name "unconnected-(P8-INT-Pad38)") (class "Default")
      (node (ref "P8") (pin "38") (pinfunction "INT_38") (pintype "passive"))
    )
    (net (code "76") (name "unconnected-(P8-RESET-Pad37)") (class "Default")
      (node (ref "P8") (pin "37") (pinfunction "RESET_37") (pintype "passive"))
    )
    (net (code "77") (name "unconnected-(P8-SCL-Pad39)") (class "Default")
      (node (ref "P8") (pin "39") (pinfunction "SCL_39") (pintype "passive"))
    )
    (net (code "78") (name "unconnected-(P8-SDA-Pad40)") (class "Default")
      (node (ref "P8") (pin "40") (pinfunction "SDA_40") (pintype "passive"))
    )
    (net (code "79") (name "unconnected-(U6-NC-Pad5)") (class "Default")
      (node (ref "U6") (pin "5") (pinfunction "NC_5") (pintype "passive"))
    )
  )
)
